# barometer_temp_humidity.net
KiCad netlist of a schematic drawn in Altium Designer
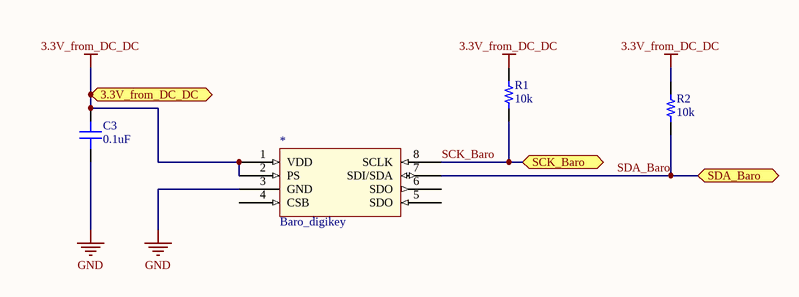
[diagram p0: barometer_temp_humidity.SchDoc]

(export (version "E")
  (design (tool "Eeschema 10.0.6"))
  (components
    (comp (ref "*")
      (value "Baro_digikey")
      (footprint "MS5607-02BA03")
      (description "223-1198-1-ND baro")
      (libsource (lib "KevinKuwata_Altium_Library2") (part "Baro_digikey"))
    )
    (comp (ref "C3")
      (value "0.1uF")
      (footprint "CAP 0402/1005")
      (description "CAP CER 0.1UF 16V X7R 0402")
      (fields
        (field (name "PART NUMBER") "C1005X7R1C104K050BC")
        (field (name "MANUFACTURER") "TDK Corporation")
      )
      (libsource (lib "Celestial Library Database") (part "Capacitor"))
    )
    (comp (ref "R1")
      (value "10k")
      (footprint "RES 0603/1608")
      (description "RES SMD 1K OHM 1% 1/10W 0603")
      (fields
        (field (name "PART NUMBER") "ERJ-3EKF1001V")
        (field (name "MANUFACTURER") "Panasonic Electronic Components")
      )
      (libsource (lib "Celestial Library Database") (part "Resistor"))
    )
    (comp (ref "R2")
      (value "10k")
      (footprint "RES 0603/1608")
      (description "RES SMD 1K OHM 1% 1/10W 0603")
      (fields
        (field (name "PART NUMBER") "ERJ-3EKF1001V")
        (field (name "MANUFACTURER") "Panasonic Electronic Components")
      )
      (libsource (lib "Celestial Library Database") (part "Resistor"))
    )
  )
  (nets
    (net (code "1") (name "/SCK_Baro") (class "Default")
      (node (ref "*") (pin "8") (pinfunction "SCLK_8") (pintype "input"))
      (node (ref "R1") (pin "1") (pinfunction "1_1") (pintype "passive"))
    )
    (net (code "2") (name "/SDA_Baro") (class "Default")
      (node (ref "*") (pin "7") (pinfunction "SDI/SDA_7") (pintype "bidirectional"))
      (node (ref "R2") (pin "1") (pinfunction "1_1") (pintype "passive"))
    )
    (net (code "3") (name "3.3V_from_DC_DC") (class "Default")
      (node (ref "*") (pin "1") (pinfunction "VDD_1") (pintype "input"))
      (node (ref "*") (pin "2") (pinfunction "PS_2") (pintype "input"))
      (node (ref "C3") (pin "2") (pinfunction "2_2") (pintype "passive"))
      (node (ref "R1") (pin "2") (pinfunction "2_2") (pintype "passive"))
      (node (ref "R2") (pin "2") (pinfunction "2_2") (pintype "passive"))
    )
    (net (code "4") (name "GND") (class "Default")
      (node (ref "*") (pin "3") (pinfunction "GND_3") (pintype "power_in"))
      (node (ref "C3") (pin "1") (pinfunction "1_1") (pintype "passive"))
    )
    (net (code "5") (name "unconnected-(*-CSB-Pad4)") (class "Default")
      (node (ref "*") (pin "4") (pinfunction "CSB_4") (pintype "input"))
    )
    (net (code "6") (name "unconnected-(*-SDO-Pad5)") (class "Default")
      (node (ref "*") (pin "5") (pinfunction "SDO_5") (pintype "input"))
    )
    (net (code "7") (name "unconnected-(*-SDO-Pad6)") (class "Default")
      (node (ref "*") (pin "6") (pinfunction "SDO_6") (pintype "output"))
    )
  )
)
